# GROUP6_GPIO_Hat_v4_0_assignment.net
KiCad netlist of a schematic drawn in EAGLE
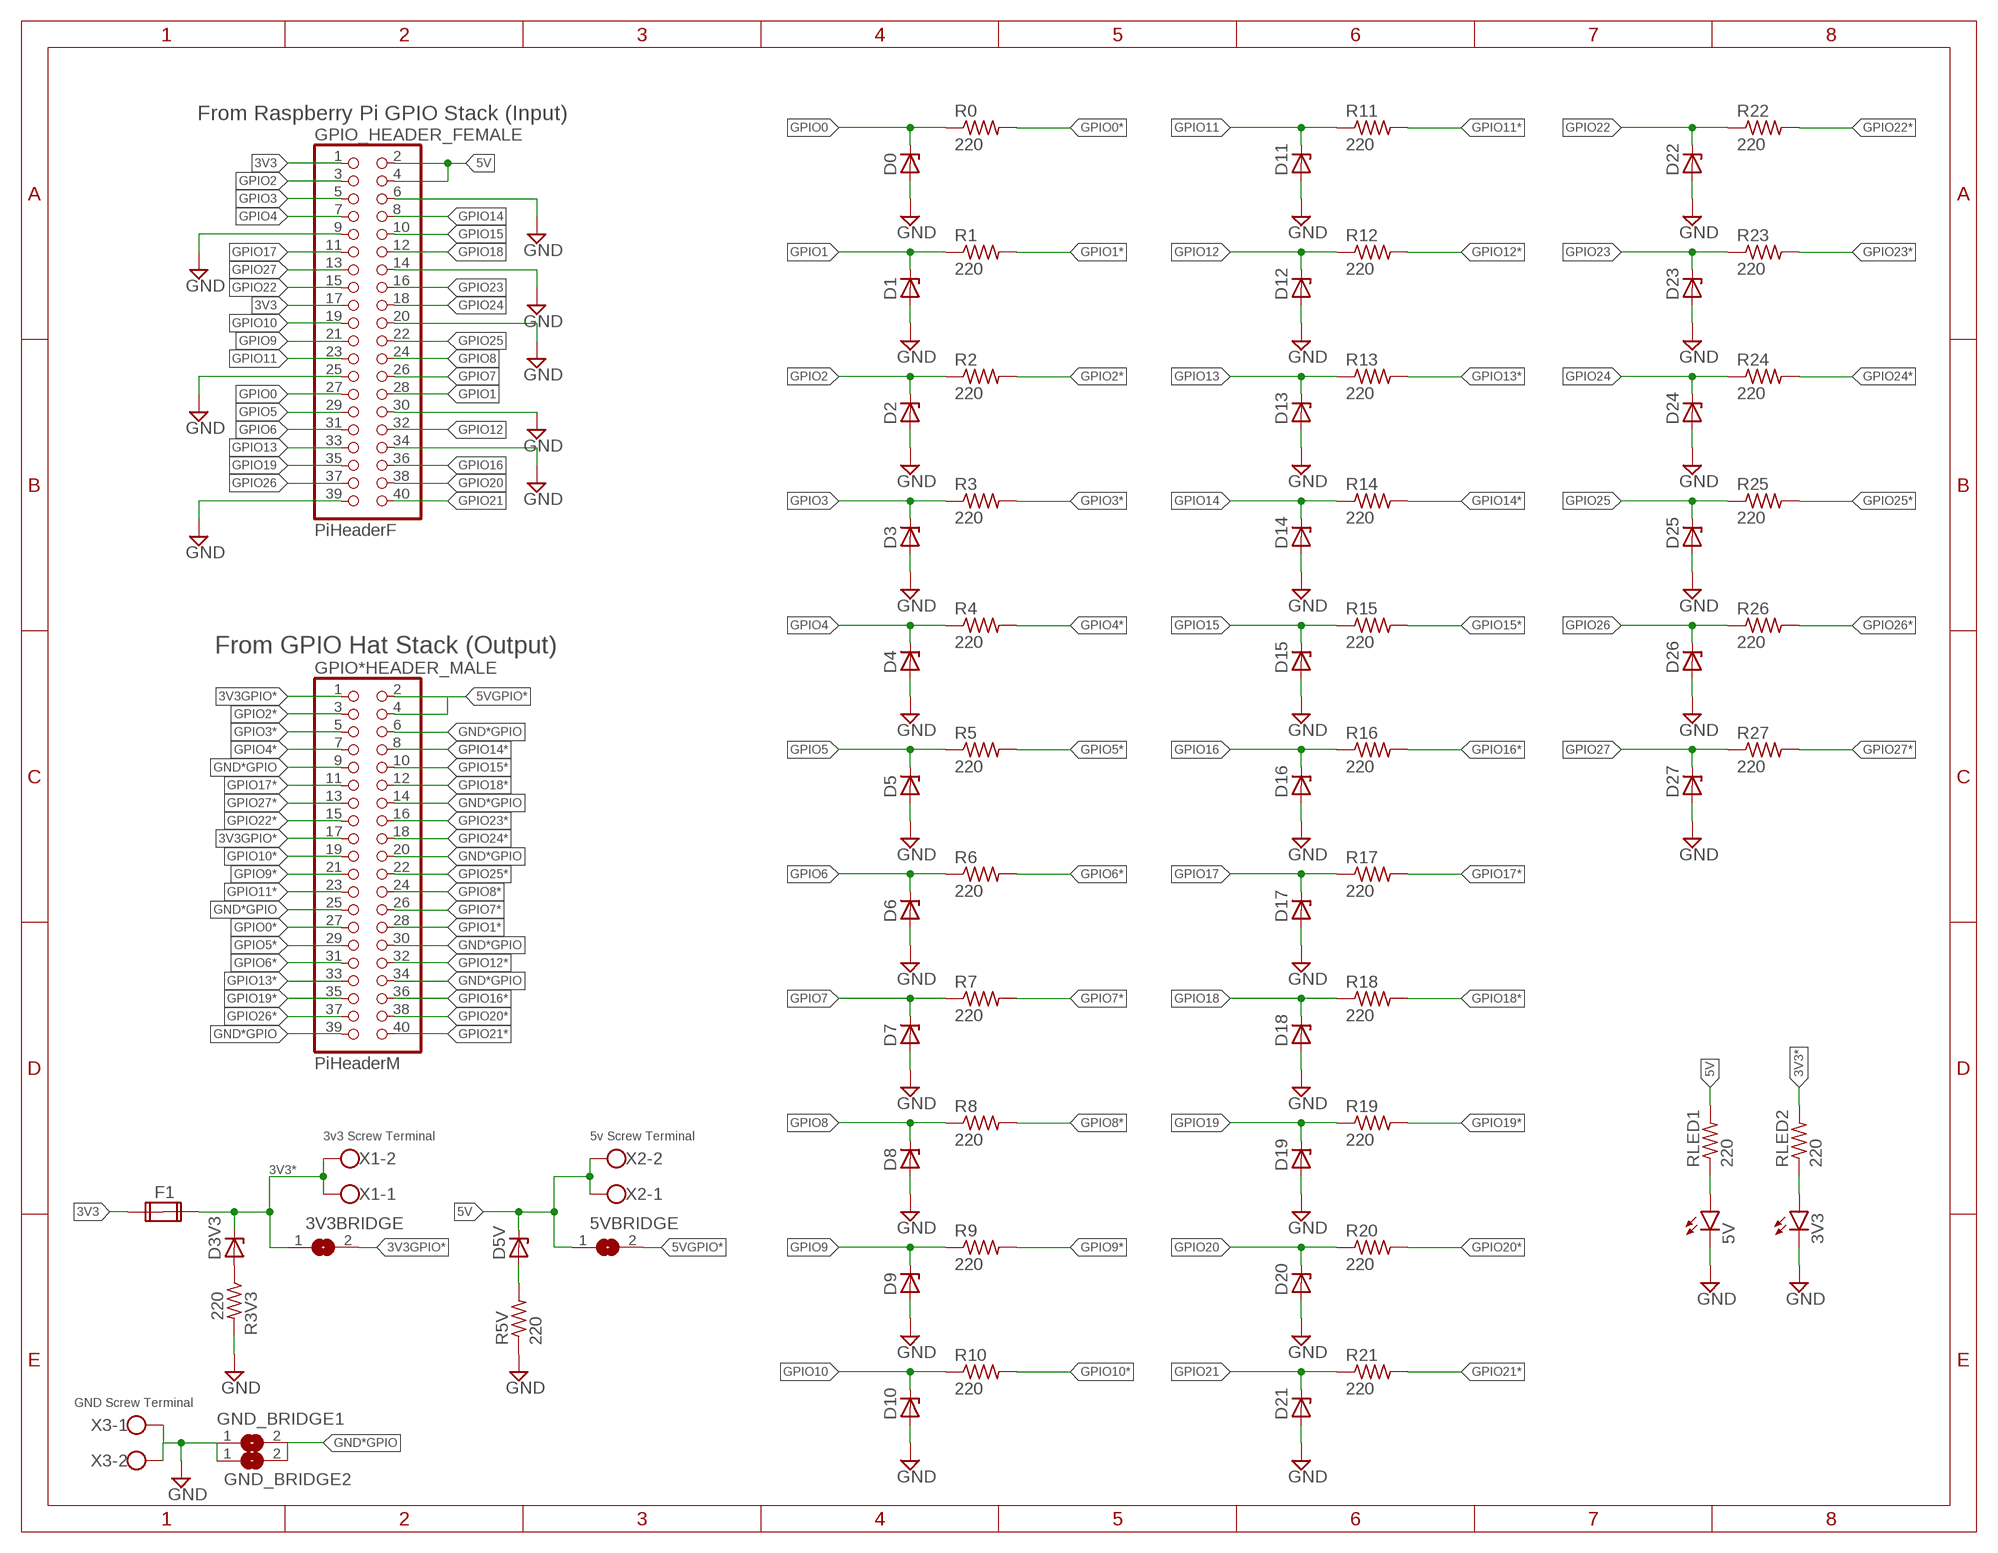
[diagram p0: schematic, sheet 1]

(export (version "E")
  (design (tool "Eeschema 10.0.6"))
  (components
    (comp (ref "3V3")
      (value "LED5MM")
      (footprint "eagle-import:LED5MM")
      (libsource (lib "eagle-import") (part "LED5MM"))
    )
    (comp (ref "3V3BRIDGE")
      (value "SJ")
      (footprint "eagle-import:SJ")
      (libsource (lib "eagle-import") (part "SJ"))
    )
    (comp (ref "5V")
      (value "LED5MM")
      (footprint "eagle-import:LED5MM")
      (libsource (lib "eagle-import") (part "LED5MM"))
    )
    (comp (ref "5VBRIDGE")
      (value "SJ")
      (footprint "eagle-import:SJ")
      (libsource (lib "eagle-import") (part "SJ"))
    )
    (comp (ref "D0")
      (value "1N4728")
      (footprint "eagle-import:DO41Z10")
      (fields (field (name "MF") "ON Semiconductor"))
      (libsource (lib "eagle-import") (part "1N4728"))
    )
    (comp (ref "D1")
      (value "1N4728")
      (footprint "eagle-import:DO41Z10")
      (fields (field (name "MF") "ON Semiconductor"))
      (libsource (lib "eagle-import") (part "1N4728"))
    )
    (comp (ref "D2")
      (value "1N4728")
      (footprint "eagle-import:DO41Z10")
      (fields (field (name "MF") "ON Semiconductor"))
      (libsource (lib "eagle-import") (part "1N4728"))
    )
    (comp (ref "D3")
      (value "1N4728")
      (footprint "eagle-import:DO41Z10")
      (fields (field (name "MF") "ON Semiconductor"))
      (libsource (lib "eagle-import") (part "1N4728"))
    )
    (comp (ref "D3V3")
      (value "1N4728")
      (footprint "eagle-import:DO41Z10")
      (fields (field (name "MF") "ON Semiconductor"))
      (libsource (lib "eagle-import") (part "1N4728"))
    )
    (comp (ref "D4")
      (value "1N4728")
      (footprint "eagle-import:DO41Z10")
      (fields (field (name "MF") "ON Semiconductor"))
      (libsource (lib "eagle-import") (part "1N4728"))
    )
    (comp (ref "D5")
      (value "1N4728")
      (footprint "eagle-import:DO41Z10")
      (fields (field (name "MF") "ON Semiconductor"))
      (libsource (lib "eagle-import") (part "1N4728"))
    )
    (comp (ref "D5V")
      (value "1N4728")
      (footprint "eagle-import:DO41Z10")
      (fields (field (name "MF") "ON Semiconductor"))
      (libsource (lib "eagle-import") (part "1N4728"))
    )
    (comp (ref "D6")
      (value "1N4728")
      (footprint "eagle-import:DO41Z10")
      (fields (field (name "MF") "ON Semiconductor"))
      (libsource (lib "eagle-import") (part "1N4728"))
    )
    (comp (ref "D7")
      (value "1N4728")
      (footprint "eagle-import:DO41Z10")
      (fields (field (name "MF") "ON Semiconductor"))
      (libsource (lib "eagle-import") (part "1N4728"))
    )
    (comp (ref "D8")
      (value "1N4728")
      (footprint "eagle-import:DO41Z10")
      (fields (field (name "MF") "ON Semiconductor"))
      (libsource (lib "eagle-import") (part "1N4728"))
    )
    (comp (ref "D9")
      (value "1N4728")
      (footprint "eagle-import:DO41Z10")
      (fields (field (name "MF") "ON Semiconductor"))
      (libsource (lib "eagle-import") (part "1N4728"))
    )
    (comp (ref "D10")
      (value "1N4728")
      (footprint "eagle-import:DO41Z10")
      (fields (field (name "MF") "ON Semiconductor"))
      (libsource (lib "eagle-import") (part "1N4728"))
    )
    (comp (ref "D11")
      (value "1N4728")
      (footprint "eagle-import:DO41Z10")
      (fields (field (name "MF") "ON Semiconductor"))
      (libsource (lib "eagle-import") (part "1N4728"))
    )
    (comp (ref "D12")
      (value "1N4728")
      (footprint "eagle-import:DO41Z10")
      (fields (field (name "MF") "ON Semiconductor"))
      (libsource (lib "eagle-import") (part "1N4728"))
    )
    (comp (ref "D13")
      (value "1N4728")
      (footprint "eagle-import:DO41Z10")
      (fields (field (name "MF") "ON Semiconductor"))
      (libsource (lib "eagle-import") (part "1N4728"))
    )
    (comp (ref "D14")
      (value "1N4728")
      (footprint "eagle-import:DO41Z10")
      (fields (field (name "MF") "ON Semiconductor"))
      (libsource (lib "eagle-import") (part "1N4728"))
    )
    (comp (ref "D15")
      (value "1N4728")
      (footprint "eagle-import:DO41Z10")
      (fields (field (name "MF") "ON Semiconductor"))
      (libsource (lib "eagle-import") (part "1N4728"))
    )
    (comp (ref "D16")
      (value "1N4728")
      (footprint "eagle-import:DO41Z10")
      (fields (field (name "MF") "ON Semiconductor"))
      (libsource (lib "eagle-import") (part "1N4728"))
    )
    (comp (ref "D17")
      (value "1N4728")
      (footprint "eagle-import:DO41Z10")
      (fields (field (name "MF") "ON Semiconductor"))
      (libsource (lib "eagle-import") (part "1N4728"))
    )
    (comp (ref "D18")
      (value "1N4728")
      (footprint "eagle-import:DO41Z10")
      (fields (field (name "MF") "ON Semiconductor"))
      (libsource (lib "eagle-import") (part "1N4728"))
    )
    (comp (ref "D19")
      (value "1N4728")
      (footprint "eagle-import:DO41Z10")
      (fields (field (name "MF") "ON Semiconductor"))
      (libsource (lib "eagle-import") (part "1N4728"))
    )
    (comp (ref "D20")
      (value "1N4728")
      (footprint "eagle-import:DO41Z10")
      (fields (field (name "MF") "ON Semiconductor"))
      (libsource (lib "eagle-import") (part "1N4728"))
    )
    (comp (ref "D21")
      (value "1N4728")
      (footprint "eagle-import:DO41Z10")
      (fields (field (name "MF") "ON Semiconductor"))
      (libsource (lib "eagle-import") (part "1N4728"))
    )
    (comp (ref "D22")
      (value "1N4728")
      (footprint "eagle-import:DO41Z10")
      (fields (field (name "MF") "ON Semiconductor"))
      (libsource (lib "eagle-import") (part "1N4728"))
    )
    (comp (ref "D23")
      (value "1N4728")
      (footprint "eagle-import:DO41Z10")
      (fields (field (name "MF") "ON Semiconductor"))
      (libsource (lib "eagle-import") (part "1N4728"))
    )
    (comp (ref "D24")
      (value "1N4728")
      (footprint "eagle-import:DO41Z10")
      (fields (field (name "MF") "ON Semiconductor"))
      (libsource (lib "eagle-import") (part "1N4728"))
    )
    (comp (ref "D25")
      (value "1N4728")
      (footprint "eagle-import:DO41Z10")
      (fields (field (name "MF") "ON Semiconductor"))
      (libsource (lib "eagle-import") (part "1N4728"))
    )
    (comp (ref "D26")
      (value "1N4728")
      (footprint "eagle-import:DO41Z10")
      (fields (field (name "MF") "ON Semiconductor"))
      (libsource (lib "eagle-import") (part "1N4728"))
    )
    (comp (ref "D27")
      (value "1N4728")
      (footprint "eagle-import:DO41Z10")
      (fields (field (name "MF") "ON Semiconductor"))
      (libsource (lib "eagle-import") (part "1N4728"))
    )
    (comp (ref "F1")
      (value "FUSE2P")
      (footprint "eagle-import:FUSE1")
      (libsource (lib "eagle-import") (part "FUSE2P"))
    )
    (comp (ref "GND_BRIDGE1")
      (value "SJ")
      (footprint "eagle-import:SJ")
      (libsource (lib "eagle-import") (part "SJ"))
    )
    (comp (ref "GND_BRIDGE2")
      (value "SJ")
      (footprint "eagle-import:SJ")
      (libsource (lib "eagle-import") (part "SJ"))
    )
    (comp (ref "GPIO*HEADER_MALE")
      (value "PiHeaderM")
      (footprint "eagle-import:2X20")
      (libsource (lib "eagle-import") (part "PINHD-2X20"))
    )
    (comp (ref "GPIO_HEADER_FEMALE")
      (value "PiHeaderF")
      (footprint "eagle-import:2X20")
      (libsource (lib "eagle-import") (part "PINHD-2X20"))
    )
    (comp (ref "R0")
      (value "220")
      (footprint "eagle-import:0207_10")
      (libsource (lib "eagle-import") (part "rcl_334_R-US_0207/10"))
    )
    (comp (ref "R1")
      (value "220")
      (footprint "eagle-import:0207_10")
      (libsource (lib "eagle-import") (part "rcl_334_R-US_0207/10"))
    )
    (comp (ref "R2")
      (value "220")
      (footprint "eagle-import:0207_10")
      (libsource (lib "eagle-import") (part "rcl_334_R-US_0207/10"))
    )
    (comp (ref "R3")
      (value "220")
      (footprint "eagle-import:0207_10")
      (libsource (lib "eagle-import") (part "rcl_334_R-US_0207/10"))
    )
    (comp (ref "R3V3")
      (value "220")
      (footprint "eagle-import:0207_10")
      (libsource (lib "eagle-import") (part "rcl_334_R-US_0207/10"))
    )
    (comp (ref "R4")
      (value "220")
      (footprint "eagle-import:0207_10")
      (libsource (lib "eagle-import") (part "rcl_334_R-US_0207/10"))
    )
    (comp (ref "R5")
      (value "220")
      (footprint "eagle-import:0207_10")
      (libsource (lib "eagle-import") (part "rcl_334_R-US_0207/10"))
    )
    (comp (ref "R5V")
      (value "220")
      (footprint "eagle-import:0207_10")
      (libsource (lib "eagle-import") (part "rcl_334_R-US_0207/10"))
    )
    (comp (ref "R6")
      (value "220")
      (footprint "eagle-import:0207_10")
      (libsource (lib "eagle-import") (part "rcl_334_R-US_0207/10"))
    )
    (comp (ref "R7")
      (value "220")
      (footprint "eagle-import:0207_10")
      (libsource (lib "eagle-import") (part "rcl_334_R-US_0207/10"))
    )
    (comp (ref "R8")
      (value "220")
      (footprint "eagle-import:0207_10")
      (libsource (lib "eagle-import") (part "rcl_334_R-US_0207/10"))
    )
    (comp (ref "R9")
      (value "220")
      (footprint "eagle-import:0207_10")
      (libsource (lib "eagle-import") (part "rcl_334_R-US_0207/10"))
    )
    (comp (ref "R10")
      (value "220")
      (footprint "eagle-import:0207_10")
      (libsource (lib "eagle-import") (part "rcl_334_R-US_0207/10"))
    )
    (comp (ref "R11")
      (value "220")
      (footprint "eagle-import:0207_10")
      (libsource (lib "eagle-import") (part "rcl_334_R-US_0207/10"))
    )
    (comp (ref "R12")
      (value "220")
      (footprint "eagle-import:0207_10")
      (libsource (lib "eagle-import") (part "rcl_334_R-US_0207/10"))
    )
    (comp (ref "R13")
      (value "220")
      (footprint "eagle-import:0207_10")
      (libsource (lib "eagle-import") (part "rcl_334_R-US_0207/10"))
    )
    (comp (ref "R14")
      (value "220")
      (footprint "eagle-import:0207_10")
      (libsource (lib "eagle-import") (part "rcl_334_R-US_0207/10"))
    )
    (comp (ref "R15")
      (value "220")
      (footprint "eagle-import:0207_10")
      (libsource (lib "eagle-import") (part "rcl_334_R-US_0207/10"))
    )
    (comp (ref "R16")
      (value "220")
      (footprint "eagle-import:0207_10")
      (libsource (lib "eagle-import") (part "rcl_334_R-US_0207/10"))
    )
    (comp (ref "R17")
      (value "220")
      (footprint "eagle-import:0207_10")
      (libsource (lib "eagle-import") (part "rcl_334_R-US_0207/10"))
    )
    (comp (ref "R18")
      (value "220")
      (footprint "eagle-import:0207_10")
      (libsource (lib "eagle-import") (part "rcl_334_R-US_0207/10"))
    )
    (comp (ref "R19")
      (value "220")
      (footprint "eagle-import:0207_10")
      (libsource (lib "eagle-import") (part "rcl_334_R-US_0207/10"))
    )
    (comp (ref "R20")
      (value "220")
      (footprint "eagle-import:0207_10")
      (libsource (lib "eagle-import") (part "rcl_334_R-US_0207/10"))
    )
    (comp (ref "R21")
      (value "220")
      (footprint "eagle-import:0207_10")
      (libsource (lib "eagle-import") (part "rcl_334_R-US_0207/10"))
    )
    (comp (ref "R22")
      (value "220")
      (footprint "eagle-import:0207_10")
      (libsource (lib "eagle-import") (part "rcl_334_R-US_0207/10"))
    )
    (comp (ref "R23")
      (value "220")
      (footprint "eagle-import:0207_10")
      (libsource (lib "eagle-import") (part "rcl_334_R-US_0207/10"))
    )
    (comp (ref "R24")
      (value "220")
      (footprint "eagle-import:0207_10")
      (libsource (lib "eagle-import") (part "rcl_334_R-US_0207/10"))
    )
    (comp (ref "R25")
      (value "220")
      (footprint "eagle-import:0207_10")
      (libsource (lib "eagle-import") (part "rcl_334_R-US_0207/10"))
    )
    (comp (ref "R26")
      (value "220")
      (footprint "eagle-import:0207_10")
      (libsource (lib "eagle-import") (part "rcl_334_R-US_0207/10"))
    )
    (comp (ref "R27")
      (value "220")
      (footprint "eagle-import:0207_10")
      (libsource (lib "eagle-import") (part "rcl_334_R-US_0207/10"))
    )
    (comp (ref "RLED1")
      (value "220")
      (footprint "eagle-import:0207_10")
      (libsource (lib "eagle-import") (part "R-US_0207/10"))
    )
    (comp (ref "RLED2")
      (value "220")
      (footprint "eagle-import:0207_10")
      (libsource (lib "eagle-import") (part "R-US_0207/10"))
    )
    (comp (ref "X1")
      (value "W237-102")
      (footprint "eagle-import:W237-102")
      (fields (field (name "MPN") "237-102"))
      (libsource (lib "eagle-import") (part "W237-102"))
    )
    (comp (ref "X2")
      (value "W237-102")
      (footprint "eagle-import:W237-102")
      (fields (field (name "MPN") "237-102"))
      (libsource (lib "eagle-import") (part "W237-102"))
    )
    (comp (ref "X3")
      (value "W237-102")
      (footprint "eagle-import:W237-102")
      (fields (field (name "MPN") "237-102"))
      (libsource (lib "eagle-import") (part "W237-102"))
    )
  )
  (nets
    (net (code "1") (name "3V3") (class "Default")
      (node (ref "F1") (pin "1A") (pinfunction "1A_1A") (pintype "passive"))
      (node (ref "GPIO_HEADER_FEMALE") (pin "1") (pinfunction "1_1") (pintype "passive"))
      (node (ref "GPIO_HEADER_FEMALE") (pin "17") (pinfunction "17_17") (pintype "passive"))
    )
    (net (code "2") (name "3V3*") (class "Default")
      (node (ref "3V3BRIDGE") (pin "1") (pinfunction "1_1") (pintype "passive"))
      (node (ref "D3V3") (pin "C") (pinfunction "C_C") (pintype "passive"))
      (node (ref "F1") (pin "2A") (pinfunction "2A_2A") (pintype "passive"))
      (node (ref "RLED2") (pin "2") (pinfunction "2_2") (pintype "passive"))
      (node (ref "X1") (pin "1") (pinfunction "KL_1") (pintype "passive"))
      (node (ref "X1") (pin "2") (pinfunction "KL_2") (pintype "passive"))
    )
    (net (code "3") (name "3V3GPIO*") (class "Default")
      (node (ref "3V3BRIDGE") (pin "2") (pinfunction "2_2") (pintype "passive"))
      (node (ref "GPIO*HEADER_MALE") (pin "1") (pinfunction "1_1") (pintype "passive"))
      (node (ref "GPIO*HEADER_MALE") (pin "17") (pinfunction "17_17") (pintype "passive"))
    )
    (net (code "4") (name "5V") (class "Default")
      (node (ref "5VBRIDGE") (pin "1") (pinfunction "1_1") (pintype "passive"))
      (node (ref "D5V") (pin "C") (pinfunction "C_C") (pintype "passive"))
      (node (ref "GPIO_HEADER_FEMALE") (pin "2") (pinfunction "2_2") (pintype "passive"))
      (node (ref "GPIO_HEADER_FEMALE") (pin "4") (pinfunction "4_4") (pintype "passive"))
      (node (ref "RLED1") (pin "2") (pinfunction "2_2") (pintype "passive"))
      (node (ref "X2") (pin "1") (pinfunction "KL_1") (pintype "passive"))
      (node (ref "X2") (pin "2") (pinfunction "KL_2") (pintype "passive"))
    )
    (net (code "5") (name "5VGPIO*") (class "Default")
      (node (ref "5VBRIDGE") (pin "2") (pinfunction "2_2") (pintype "passive"))
      (node (ref "GPIO*HEADER_MALE") (pin "2") (pinfunction "2_2") (pintype "passive"))
      (node (ref "GPIO*HEADER_MALE") (pin "4") (pinfunction "4_4") (pintype "passive"))
    )
    (net (code "6") (name "GND") (class "Default")
      (node (ref "3V3") (pin "K") (pinfunction "C_K") (pintype "passive"))
      (node (ref "5V") (pin "K") (pinfunction "C_K") (pintype "passive"))
      (node (ref "D0") (pin "A") (pinfunction "A_A") (pintype "passive"))
      (node (ref "D1") (pin "A") (pinfunction "A_A") (pintype "passive"))
      (node (ref "D10") (pin "A") (pinfunction "A_A") (pintype "passive"))
      (node (ref "D11") (pin "A") (pinfunction "A_A") (pintype "passive"))
      (node (ref "D12") (pin "A") (pinfunction "A_A") (pintype "passive"))
      (node (ref "D13") (pin "A") (pinfunction "A_A") (pintype "passive"))
      (node (ref "D14") (pin "A") (pinfunction "A_A") (pintype "passive"))
      (node (ref "D15") (pin "A") (pinfunction "A_A") (pintype "passive"))
      (node (ref "D16") (pin "A") (pinfunction "A_A") (pintype "passive"))
      (node (ref "D17") (pin "A") (pinfunction "A_A") (pintype "passive"))
      (node (ref "D18") (pin "A") (pinfunction "A_A") (pintype "passive"))
      (node (ref "D19") (pin "A") (pinfunction "A_A") (pintype "passive"))
      (node (ref "D2") (pin "A") (pinfunction "A_A") (pintype "passive"))
      (node (ref "D20") (pin "A") (pinfunction "A_A") (pintype "passive"))
      (node (ref "D21") (pin "A") (pinfunction "A_A") (pintype "passive"))
      (node (ref "D22") (pin "A") (pinfunction "A_A") (pintype "passive"))
      (node (ref "D23") (pin "A") (pinfunction "A_A") (pintype "passive"))
      (node (ref "D24") (pin "A") (pinfunction "A_A") (pintype "passive"))
      (node (ref "D25") (pin "A") (pinfunction "A_A") (pintype "passive"))
      (node (ref "D26") (pin "A") (pinfunction "A_A") (pintype "passive"))
      (node (ref "D27") (pin "A") (pinfunction "A_A") (pintype "passive"))
      (node (ref "D3") (pin "A") (pinfunction "A_A") (pintype "passive"))
      (node (ref "D4") (pin "A") (pinfunction "A_A") (pintype "passive"))
      (node (ref "D5") (pin "A") (pinfunction "A_A") (pintype "passive"))
      (node (ref "D6") (pin "A") (pinfunction "A_A") (pintype "passive"))
      (node (ref "D7") (pin "A") (pinfunction "A_A") (pintype "passive"))
      (node (ref "D8") (pin "A") (pinfunction "A_A") (pintype "passive"))
      (node (ref "D9") (pin "A") (pinfunction "A_A") (pintype "passive"))
      (node (ref "GND_BRIDGE1") (pin "1") (pinfunction "1_1") (pintype "passive"))
      (node (ref "GND_BRIDGE2") (pin "1") (pinfunction "1_1") (pintype "passive"))
      (node (ref "GPIO_HEADER_FEMALE") (pin "14") (pinfunction "14_14") (pintype "passive"))
      (node (ref "GPIO_HEADER_FEMALE") (pin "20") (pinfunction "20_20") (pintype "passive"))
      (node (ref "GPIO_HEADER_FEMALE") (pin "25") (pinfunction "25_25") (pintype "passive"))
      (node (ref "GPIO_HEADER_FEMALE") (pin "30") (pinfunction "30_30") (pintype "passive"))
      (node (ref "GPIO_HEADER_FEMALE") (pin "34") (pinfunction "34_34") (pintype "passive"))
      (node (ref "GPIO_HEADER_FEMALE") (pin "39") (pinfunction "39_39") (pintype "passive"))
      (node (ref "GPIO_HEADER_FEMALE") (pin "6") (pinfunction "6_6") (pintype "passive"))
      (node (ref "GPIO_HEADER_FEMALE") (pin "9") (pinfunction "9_9") (pintype "passive"))
      (node (ref "R3V3") (pin "2") (pinfunction "2_2") (pintype "passive"))
      (node (ref "R5V") (pin "1") (pinfunction "1_1") (pintype "passive"))
      (node (ref "X3") (pin "1") (pinfunction "KL_1") (pintype "passive"))
      (node (ref "X3") (pin "2") (pinfunction "KL_2") (pintype "passive"))
    )
    (net (code "7") (name "GND*GPIO") (class "Default")
      (node (ref "GND_BRIDGE1") (pin "2") (pinfunction "2_2") (pintype "passive"))
      (node (ref "GND_BRIDGE2") (pin "2") (pinfunction "2_2") (pintype "passive"))
      (node (ref "GPIO*HEADER_MALE") (pin "14") (pinfunction "14_14") (pintype "passive"))
      (node (ref "GPIO*HEADER_MALE") (pin "20") (pinfunction "20_20") (pintype "passive"))
      (node (ref "GPIO*HEADER_MALE") (pin "25") (pinfunction "25_25") (pintype "passive"))
      (node (ref "GPIO*HEADER_MALE") (pin "30") (pinfunction "30_30") (pintype "passive"))
      (node (ref "GPIO*HEADER_MALE") (pin "34") (pinfunction "34_34") (pintype "passive"))
      (node (ref "GPIO*HEADER_MALE") (pin "39") (pinfunction "39_39") (pintype "passive"))
      (node (ref "GPIO*HEADER_MALE") (pin "6") (pinfunction "6_6") (pintype "passive"))
      (node (ref "GPIO*HEADER_MALE") (pin "9") (pinfunction "9_9") (pintype "passive"))
    )
    (net (code "8") (name "GPIO0") (class "Default")
      (node (ref "D0") (pin "C") (pinfunction "C_C") (pintype "passive"))
      (node (ref "GPIO_HEADER_FEMALE") (pin "27") (pinfunction "27_27") (pintype "passive"))
      (node (ref "R0") (pin "1") (pinfunction "1_1") (pintype "passive"))
    )
    (net (code "9") (name "GPIO0*") (class "Default")
      (node (ref "GPIO*HEADER_MALE") (pin "27") (pinfunction "27_27") (pintype "passive"))
      (node (ref "R0") (pin "2") (pinfunction "2_2") (pintype "passive"))
    )
    (net (code "10") (name "GPIO1") (class "Default")
      (node (ref "D1") (pin "C") (pinfunction "C_C") (pintype "passive"))
      (node (ref "GPIO_HEADER_FEMALE") (pin "28") (pinfunction "28_28") (pintype "passive"))
      (node (ref "R1") (pin "1") (pinfunction "1_1") (pintype "passive"))
    )
    (net (code "11") (name "GPIO1*") (class "Default")
      (node (ref "GPIO*HEADER_MALE") (pin "28") (pinfunction "28_28") (pintype "passive"))
      (node (ref "R1") (pin "2") (pinfunction "2_2") (pintype "passive"))
    )
    (net (code "12") (name "GPIO2") (class "Default")
      (node (ref "D2") (pin "C") (pinfunction "C_C") (pintype "passive"))
      (node (ref "GPIO_HEADER_FEMALE") (pin "3") (pinfunction "3_3") (pintype "passive"))
      (node (ref "R2") (pin "1") (pinfunction "1_1") (pintype "passive"))
    )
    (net (code "13") (name "GPIO2*") (class "Default")
      (node (ref "GPIO*HEADER_MALE") (pin "3") (pinfunction "3_3") (pintype "passive"))
      (node (ref "R2") (pin "2") (pinfunction "2_2") (pintype "passive"))
    )
    (net (code "14") (name "GPIO3") (class "Default")
      (node (ref "D3") (pin "C") (pinfunction "C_C") (pintype "passive"))
      (node (ref "GPIO_HEADER_FEMALE") (pin "5") (pinfunction "5_5") (pintype "passive"))
      (node (ref "R3") (pin "1") (pinfunction "1_1") (pintype "passive"))
    )
    (net (code "15") (name "GPIO3*") (class "Default")
      (node (ref "GPIO*HEADER_MALE") (pin "5") (pinfunction "5_5") (pintype "passive"))
      (node (ref "R3") (pin "2") (pinfunction "2_2") (pintype "passive"))
    )
    (net (code "16") (name "GPIO4") (class "Default")
      (node (ref "D4") (pin "C") (pinfunction "C_C") (pintype "passive"))
      (node (ref "GPIO_HEADER_FEMALE") (pin "7") (pinfunction "7_7") (pintype "passive"))
      (node (ref "R4") (pin "1") (pinfunction "1_1") (pintype "passive"))
    )
    (net (code "17") (name "GPIO4*") (class "Default")
      (node (ref "GPIO*HEADER_MALE") (pin "7") (pinfunction "7_7") (pintype "passive"))
      (node (ref "R4") (pin "2") (pinfunction "2_2") (pintype "passive"))
    )
    (net (code "18") (name "GPIO5") (class "Default")
      (node (ref "D5") (pin "C") (pinfunction "C_C") (pintype "passive"))
      (node (ref "GPIO_HEADER_FEMALE") (pin "29") (pinfunction "29_29") (pintype "passive"))
      (node (ref "R5") (pin "1") (pinfunction "1_1") (pintype "passive"))
    )
    (net (code "19") (name "GPIO5*") (class "Default")
      (node (ref "GPIO*HEADER_MALE") (pin "29") (pinfunction "29_29") (pintype "passive"))
      (node (ref "R5") (pin "2") (pinfunction "2_2") (pintype "passive"))
    )
    (net (code "20") (name "GPIO6") (class "Default")
      (node (ref "D6") (pin "C") (pinfunction "C_C") (pintype "passive"))
      (node (ref "GPIO_HEADER_FEMALE") (pin "31") (pinfunction "31_31") (pintype "passive"))
      (node (ref "R6") (pin "1") (pinfunction "1_1") (pintype "passive"))
    )
    (net (code "21") (name "GPIO6*") (class "Default")
      (node (ref "GPIO*HEADER_MALE") (pin "31") (pinfunction "31_31") (pintype "passive"))
      (node (ref "R6") (pin "2") (pinfunction "2_2") (pintype "passive"))
    )
    (net (code "22") (name "GPIO7") (class "Default")
      (node (ref "D7") (pin "C") (pinfunction "C_C") (pintype "passive"))
      (node (ref "GPIO_HEADER_FEMALE") (pin "26") (pinfunction "26_26") (pintype "passive"))
      (node (ref "R7") (pin "1") (pinfunction "1_1") (pintype "passive"))
    )
    (net (code "23") (name "GPIO7*") (class "Default")
      (node (ref "GPIO*HEADER_MALE") (pin "26") (pinfunction "26_26") (pintype "passive"))
      (node (ref "R7") (pin "2") (pinfunction "2_2") (pintype "passive"))
    )
    (net (code "24") (name "GPIO8") (class "Default")
      (node (ref "D8") (pin "C") (pinfunction "C_C") (pintype "passive"))
      (node (ref "GPIO_HEADER_FEMALE") (pin "24") (pinfunction "24_24") (pintype "passive"))
      (node (ref "R8") (pin "1") (pinfunction "1_1") (pintype "passive"))
    )
    (net (code "25") (name "GPIO8*") (class "Default")
      (node (ref "GPIO*HEADER_MALE") (pin "24") (pinfunction "24_24") (pintype "passive"))
      (node (ref "R8") (pin "2") (pinfunction "2_2") (pintype "passive"))
    )
    (net (code "26") (name "GPIO9") (class "Default")
      (node (ref "D9") (pin "C") (pinfunction "C_C") (pintype "passive"))
      (node (ref "GPIO_HEADER_FEMALE") (pin "21") (pinfunction "21_21") (pintype "passive"))
      (node (ref "R9") (pin "1") (pinfunction "1_1") (pintype "passive"))
    )
    (net (code "27") (name "GPIO9*") (class "Default")
      (node (ref "GPIO*HEADER_MALE") (pin "21") (pinfunction "21_21") (pintype "passive"))
      (node (ref "R9") (pin "2") (pinfunction "2_2") (pintype "passive"))
    )
    (net (code "28") (name "GPIO10") (class "Default")
      (node (ref "D10") (pin "C") (pinfunction "C_C") (pintype "passive"))
      (node (ref "GPIO_HEADER_FEMALE") (pin "19") (pinfunction "19_19") (pintype "passive"))
      (node (ref "R10") (pin "1") (pinfunction "1_1") (pintype "passive"))
    )
    (net (code "29") (name "GPIO10*") (class "Default")
      (node (ref "GPIO*HEADER_MALE") (pin "19") (pinfunction "19_19") (pintype "passive"))
      (node (ref "R10") (pin "2") (pinfunction "2_2") (pintype "passive"))
    )
    (net (code "30") (name "GPIO11") (class "Default")
      (node (ref "D11") (pin "C") (pinfunction "C_C") (pintype "passive"))
      (node (ref "GPIO_HEADER_FEMALE") (pin "23") (pinfunction "23_23") (pintype "passive"))
      (node (ref "R11") (pin "1") (pinfunction "1_1") (pintype "passive"))
    )
    (net (code "31") (name "GPIO11*") (class "Default")
      (node (ref "GPIO*HEADER_MALE") (pin "23") (pinfunction "23_23") (pintype "passive"))
      (node (ref "R11") (pin "2") (pinfunction "2_2") (pintype "passive"))
    )
    (net (code "32") (name "GPIO12") (class "Default")
      (node (ref "D12") (pin "C") (pinfunction "C_C") (pintype "passive"))
      (node (ref "GPIO_HEADER_FEMALE") (pin "32") (pinfunction "32_32") (pintype "passive"))
      (node (ref "R12") (pin "1") (pinfunction "1_1") (pintype "passive"))
    )
    (net (code "33") (name "GPIO12*") (class "Default")
      (node (ref "GPIO*HEADER_MALE") (pin "32") (pinfunction "32_32") (pintype "passive"))
      (node (ref "R12") (pin "2") (pinfunction "2_2") (pintype "passive"))
    )
    (net (code "34") (name "GPIO13") (class "Default")
      (node (ref "D13") (pin "C") (pinfunction "C_C") (pintype "passive"))
      (node (ref "GPIO_HEADER_FEMALE") (pin "33") (pinfunction "33_33") (pintype "passive"))
      (node (ref "R13") (pin "1") (pinfunction "1_1") (pintype "passive"))
    )
    (net (code "35") (name "GPIO13*") (class "Default")
      (node (ref "GPIO*HEADER_MALE") (pin "33") (pinfunction "33_33") (pintype "passive"))
      (node (ref "R13") (pin "2") (pinfunction "2_2") (pintype "passive"))
    )
    (net (code "36") (name "GPIO14") (class "Default")
      (node (ref "D14") (pin "C") (pinfunction "C_C") (pintype "passive"))
      (node (ref "GPIO_HEADER_FEMALE") (pin "8") (pinfunction "8_8") (pintype "passive"))
      (node (ref "R14") (pin "1") (pinfunction "1_1") (pintype "passive"))
    )
    (net (code "37") (name "GPIO14*") (class "Default")
      (node (ref "GPIO*HEADER_MALE") (pin "8") (pinfunction "8_8") (pintype "passive"))
      (node (ref "R14") (pin "2") (pinfunction "2_2") (pintype "passive"))
    )
    (net (code "38") (name "GPIO15") (class "Default")
      (node (ref "D15") (pin "C") (pinfunction "C_C") (pintype "passive"))
      (node (ref "GPIO_HEADER_FEMALE") (pin "10") (pinfunction "10_10") (pintype "passive"))
      (node (ref "R15") (pin "1") (pinfunction "1_1") (pintype "passive"))
    )
    (net (code "39") (name "GPIO15*") (class "Default")
      (node (ref "GPIO*HEADER_MALE") (pin "10") (pinfunction "10_10") (pintype "passive"))
      (node (ref "R15") (pin "2") (pinfunction "2_2") (pintype "passive"))
    )
    (net (code "40") (name "GPIO16") (class "Default")
      (node (ref "D16") (pin "C") (pinfunction "C_C") (pintype "passive"))
      (node (ref "GPIO_HEADER_FEMALE") (pin "36") (pinfunction "36_36") (pintype "passive"))
      (node (ref "R16") (pin "1") (pinfunction "1_1") (pintype "passive"))
    )
    (net (code "41") (name "GPIO16*") (class "Default")
      (node (ref "GPIO*HEADER_MALE") (pin "36") (pinfunction "36_36") (pintype "passive"))
      (node (ref "R16") (pin "2") (pinfunction "2_2") (pintype "passive"))
    )
    (net (code "42") (name "GPIO17") (class "Default")
      (node (ref "D17") (pin "C") (pinfunction "C_C") (pintype "passive"))
      (node (ref "GPIO_HEADER_FEMALE") (pin "11") (pinfunction "11_11") (pintype "passive"))
      (node (ref "R17") (pin "1") (pinfunction "1_1") (pintype "passive"))
    )
    (net (code "43") (name "GPIO17*") (class "Default")
      (node (ref "GPIO*HEADER_MALE") (pin "11") (pinfunction "11_11") (pintype "passive"))
      (node (ref "R17") (pin "2") (pinfunction "2_2") (pintype "passive"))
    )
    (net (code "44") (name "GPIO18") (class "Default")
      (node (ref "D18") (pin "C") (pinfunction "C_C") (pintype "passive"))
      (node (ref "GPIO_HEADER_FEMALE") (pin "12") (pinfunction "12_12") (pintype "passive"))
      (node (ref "R18") (pin "1") (pinfunction "1_1") (pintype "passive"))
    )
    (net (code "45") (name "GPIO18*") (class "Default")
      (node (ref "GPIO*HEADER_MALE") (pin "12") (pinfunction "12_12") (pintype "passive"))
      (node (ref "R18") (pin "2") (pinfunction "2_2") (pintype "passive"))
    )
    (net (code "46") (name "GPIO19") (class "Default")
      (node (ref "D19") (pin "C") (pinfunction "C_C") (pintype "passive"))
      (node (ref "GPIO_HEADER_FEMALE") (pin "35") (pinfunction "35_35") (pintype "passive"))
      (node (ref "R19") (pin "1") (pinfunction "1_1") (pintype "passive"))
    )
    (net (code "47") (name "GPIO19*") (class "Default")
      (node (ref "GPIO*HEADER_MALE") (pin "35") (pinfunction "35_35") (pintype "passive"))
      (node (ref "R19") (pin "2") (pinfunction "2_2") (pintype "passive"))
    )
    (net (code "48") (name "GPIO20") (class "Default")
      (node (ref "D20") (pin "C") (pinfunction "C_C") (pintype "passive"))
      (node (ref "GPIO_HEADER_FEMALE") (pin "38") (pinfunction "38_38") (pintype "passive"))
      (node (ref "R20") (pin "1") (pinfunction "1_1") (pintype "passive"))
    )
    (net (code "49") (name "GPIO20*") (class "Default")
      (node (ref "GPIO*HEADER_MALE") (pin "38") (pinfunction "38_38") (pintype "passive"))
      (node (ref "R20") (pin "2") (pinfunction "2_2") (pintype "passive"))
    )
    (net (code "50") (name "GPIO21") (class "Default")
      (node (ref "D21") (pin "C") (pinfunction "C_C") (pintype "passive"))
      (node (ref "GPIO_HEADER_FEMALE") (pin "40") (pinfunction "40_40") (pintype "passive"))
      (node (ref "R21") (pin "1") (pinfunction "1_1") (pintype "passive"))
    )
    (net (code "51") (name "GPIO21*") (class "Default")
      (node (ref "GPIO*HEADER_MALE") (pin "40") (pinfunction "40_40") (pintype "passive"))
      (node (ref "R21") (pin "2") (pinfunction "2_2") (pintype "passive"))
    )
    (net (code "52") (name "GPIO22") (class "Default")
      (node (ref "D22") (pin "C") (pinfunction "C_C") (pintype "passive"))
      (node (ref "GPIO_HEADER_FEMALE") (pin "15") (pinfunction "15_15") (pintype "passive"))
      (node (ref "R22") (pin "1") (pinfunction "1_1") (pintype "passive"))
    )
    (net (code "53") (name "GPIO22*") (class "Default")
      (node (ref "GPIO*HEADER_MALE") (pin "15") (pinfunction "15_15") (pintype "passive"))
      (node (ref "R22") (pin "2") (pinfunction "2_2") (pintype "passive"))
    )
    (net (code "54") (name "GPIO23") (class "Default")
      (node (ref "D23") (pin "C") (pinfunction "C_C") (pintype "passive"))
      (node (ref "GPIO_HEADER_FEMALE") (pin "16") (pinfunction "16_16") (pintype "passive"))
      (node (ref "R23") (pin "1") (pinfunction "1_1") (pintype "passive"))
    )
    (net (code "55") (name "GPIO23*") (class "Default")
      (node (ref "GPIO*HEADER_MALE") (pin "16") (pinfunction "16_16") (pintype "passive"))
      (node (ref "R23") (pin "2") (pinfunction "2_2") (pintype "passive"))
    )
    (net (code "56") (name "GPIO24") (class "Default")
      (node (ref "D24") (pin "C") (pinfunction "C_C") (pintype "passive"))
      (node (ref "GPIO_HEADER_FEMALE") (pin "18") (pinfunction "18_18") (pintype "passive"))
      (node (ref "R24") (pin "1") (pinfunction "1_1") (pintype "passive"))
    )
    (net (code "57") (name "GPIO24*") (class "Default")
      (node (ref "GPIO*HEADER_MALE") (pin "18") (pinfunction "18_18") (pintype "passive"))
      (node (ref "R24") (pin "2") (pinfunction "2_2") (pintype "passive"))
    )
    (net (code "58") (name "GPIO25") (class "Default")
      (node (ref "D25") (pin "C") (pinfunction "C_C") (pintype "passive"))
      (node (ref "GPIO_HEADER_FEMALE") (pin "22") (pinfunction "22_22") (pintype "passive"))
      (node (ref "R25") (pin "1") (pinfunction "1_1") (pintype "passive"))
    )
    (net (code "59") (name "GPIO25*") (class "Default")
      (node (ref "GPIO*HEADER_MALE") (pin "22") (pinfunction "22_22") (pintype "passive"))
      (node (ref "R25") (pin "2") (pinfunction "2_2") (pintype "passive"))
    )
    (net (code "60") (name "GPIO26") (class "Default")
      (node (ref "D26") (pin "C") (pinfunction "C_C") (pintype "passive"))
      (node (ref "GPIO_HEADER_FEMALE") (pin "37") (pinfunction "37_37") (pintype "passive"))
      (node (ref "R26") (pin "1") (pinfunction "1_1") (pintype "passive"))
    )
    (net (code "61") (name "GPIO26*") (class "Default")
      (node (ref "GPIO*HEADER_MALE") (pin "37") (pinfunction "37_37") (pintype "passive"))
      (node (ref "R26") (pin "2") (pinfunction "2_2") (pintype "passive"))
    )
    (net (code "62") (name "GPIO27") (class "Default")
      (node (ref "D27") (pin "C") (pinfunction "C_C") (pintype "passive"))
      (node (ref "GPIO_HEADER_FEMALE") (pin "13") (pinfunction "13_13") (pintype "passive"))
      (node (ref "R27") (pin "1") (pinfunction "1_1") (pintype "passive"))
    )
    (net (code "63") (name "GPIO27*") (class "Default")
      (node (ref "GPIO*HEADER_MALE") (pin "13") (pinfunction "13_13") (pintype "passive"))
      (node (ref "R27") (pin "2") (pinfunction "2_2") (pintype "passive"))
    )
    (net (code "64") (name "Net-(3V3-PadA)") (class "Default")
      (node (ref "3V3") (pin "A") (pinfunction "A_A") (pintype "passive"))
      (node (ref "RLED2") (pin "1") (pinfunction "1_1") (pintype "passive"))
    )
    (net (code "65") (name "Net-(5V-PadA)") (class "Default")
      (node (ref "5V") (pin "A") (pinfunction "A_A") (pintype "passive"))
      (node (ref "RLED1") (pin "1") (pinfunction "1_1") (pintype "passive"))
    )
    (net (code "66") (name "Net-(D3V3-PadA)") (class "Default")
      (node (ref "D3V3") (pin "A") (pinfunction "A_A") (pintype "passive"))
      (node (ref "R3V3") (pin "1") (pinfunction "1_1") (pintype "passive"))
    )
    (net (code "67") (name "Net-(D5V-PadA)") (class "Default")
      (node (ref "D5V") (pin "A") (pinfunction "A_A") (pintype "passive"))
      (node (ref "R5V") (pin "2") (pinfunction "2_2") (pintype "passive"))
    )
    (net (code "68") (name "unconnected-(F1-Pad1B)") (class "Default")
      (node (ref "F1") (pin "1B") (pinfunction "1B_1B") (pintype "passive"))
    )
    (net (code "69") (name "unconnected-(F1-Pad2B)") (class "Default")
      (node (ref "F1") (pin "2B") (pinfunction "2B_2B") (pintype "passive"))
    )
  )
)
